# pam-controller.net
KiCad netlist of a schematic drawn in EAGLE
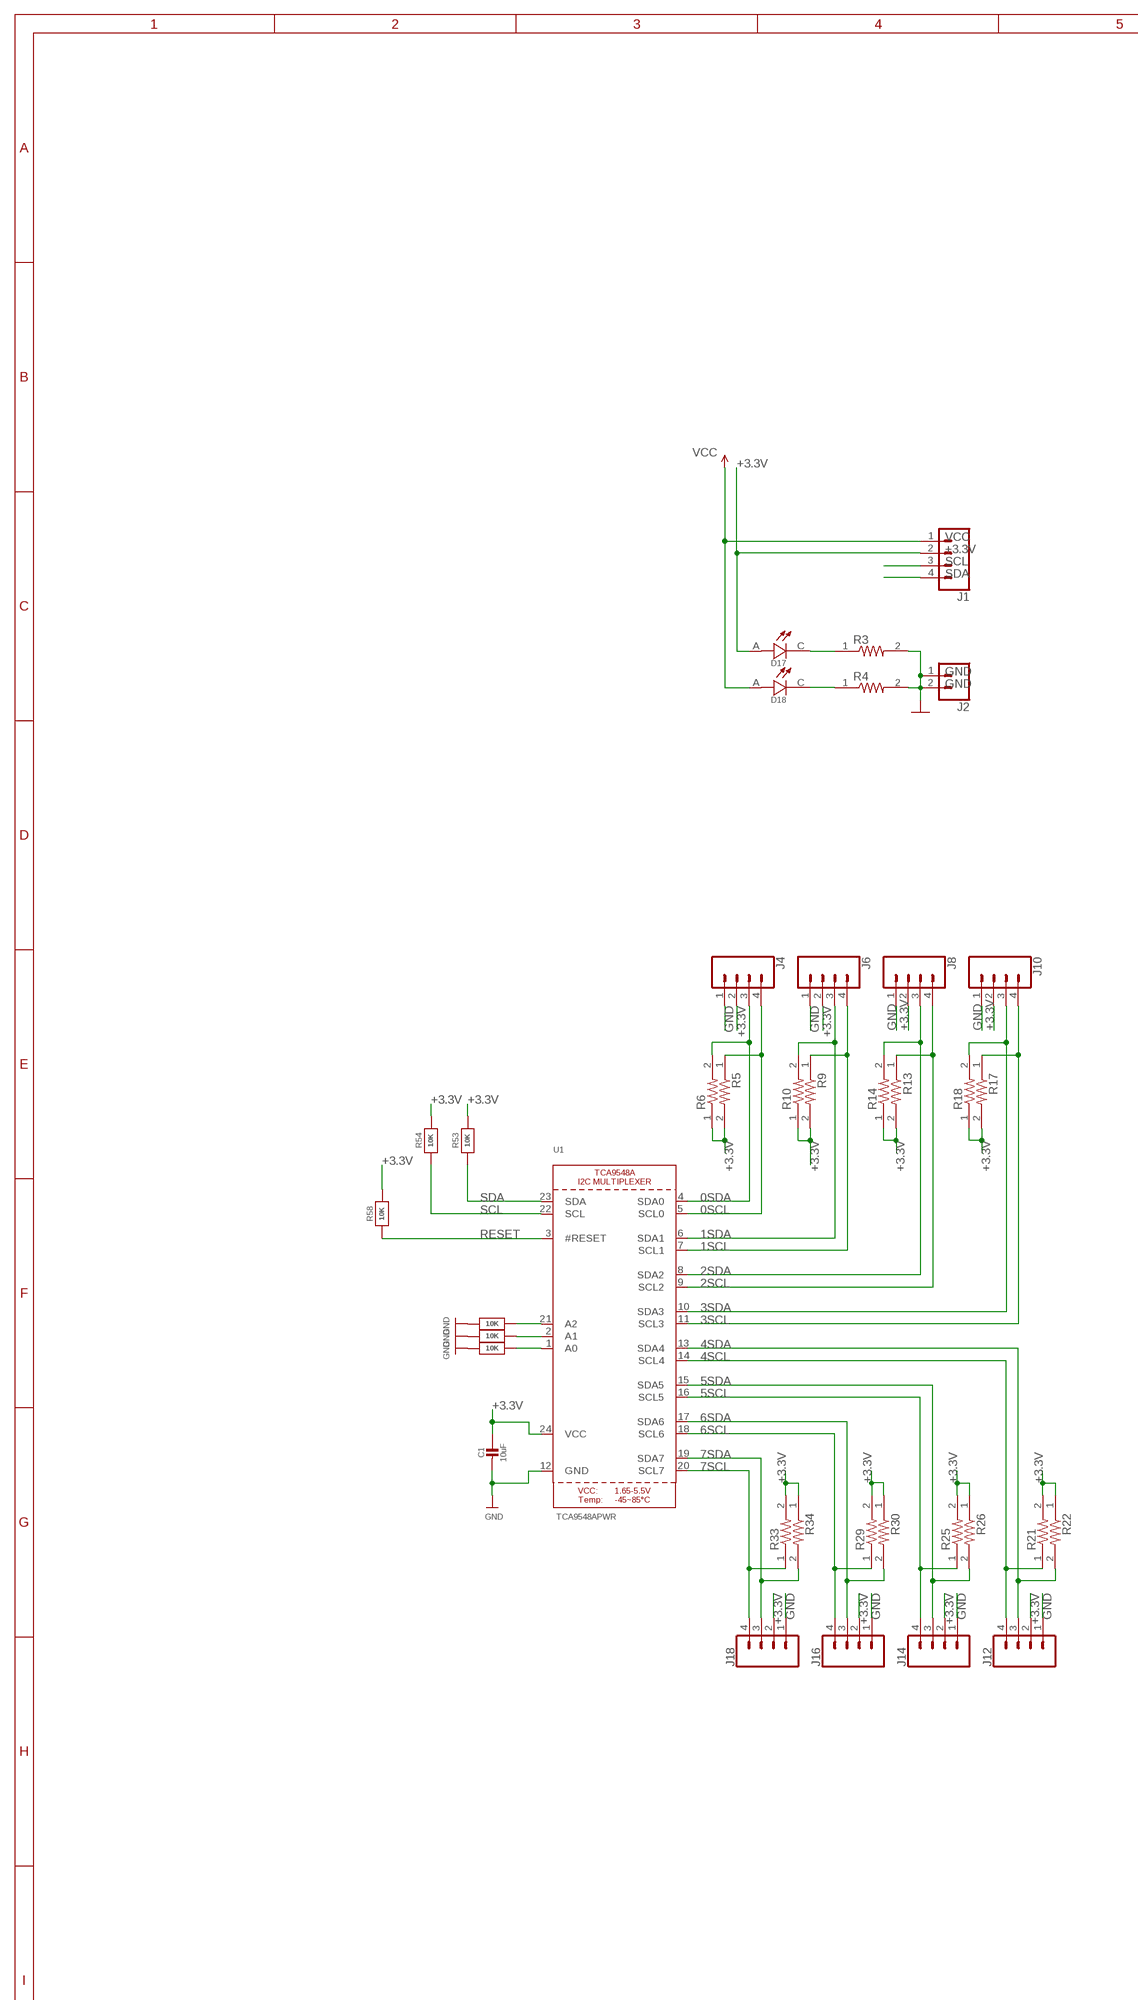
[diagram p0: schematic, sheet 1, part 1 of 2]
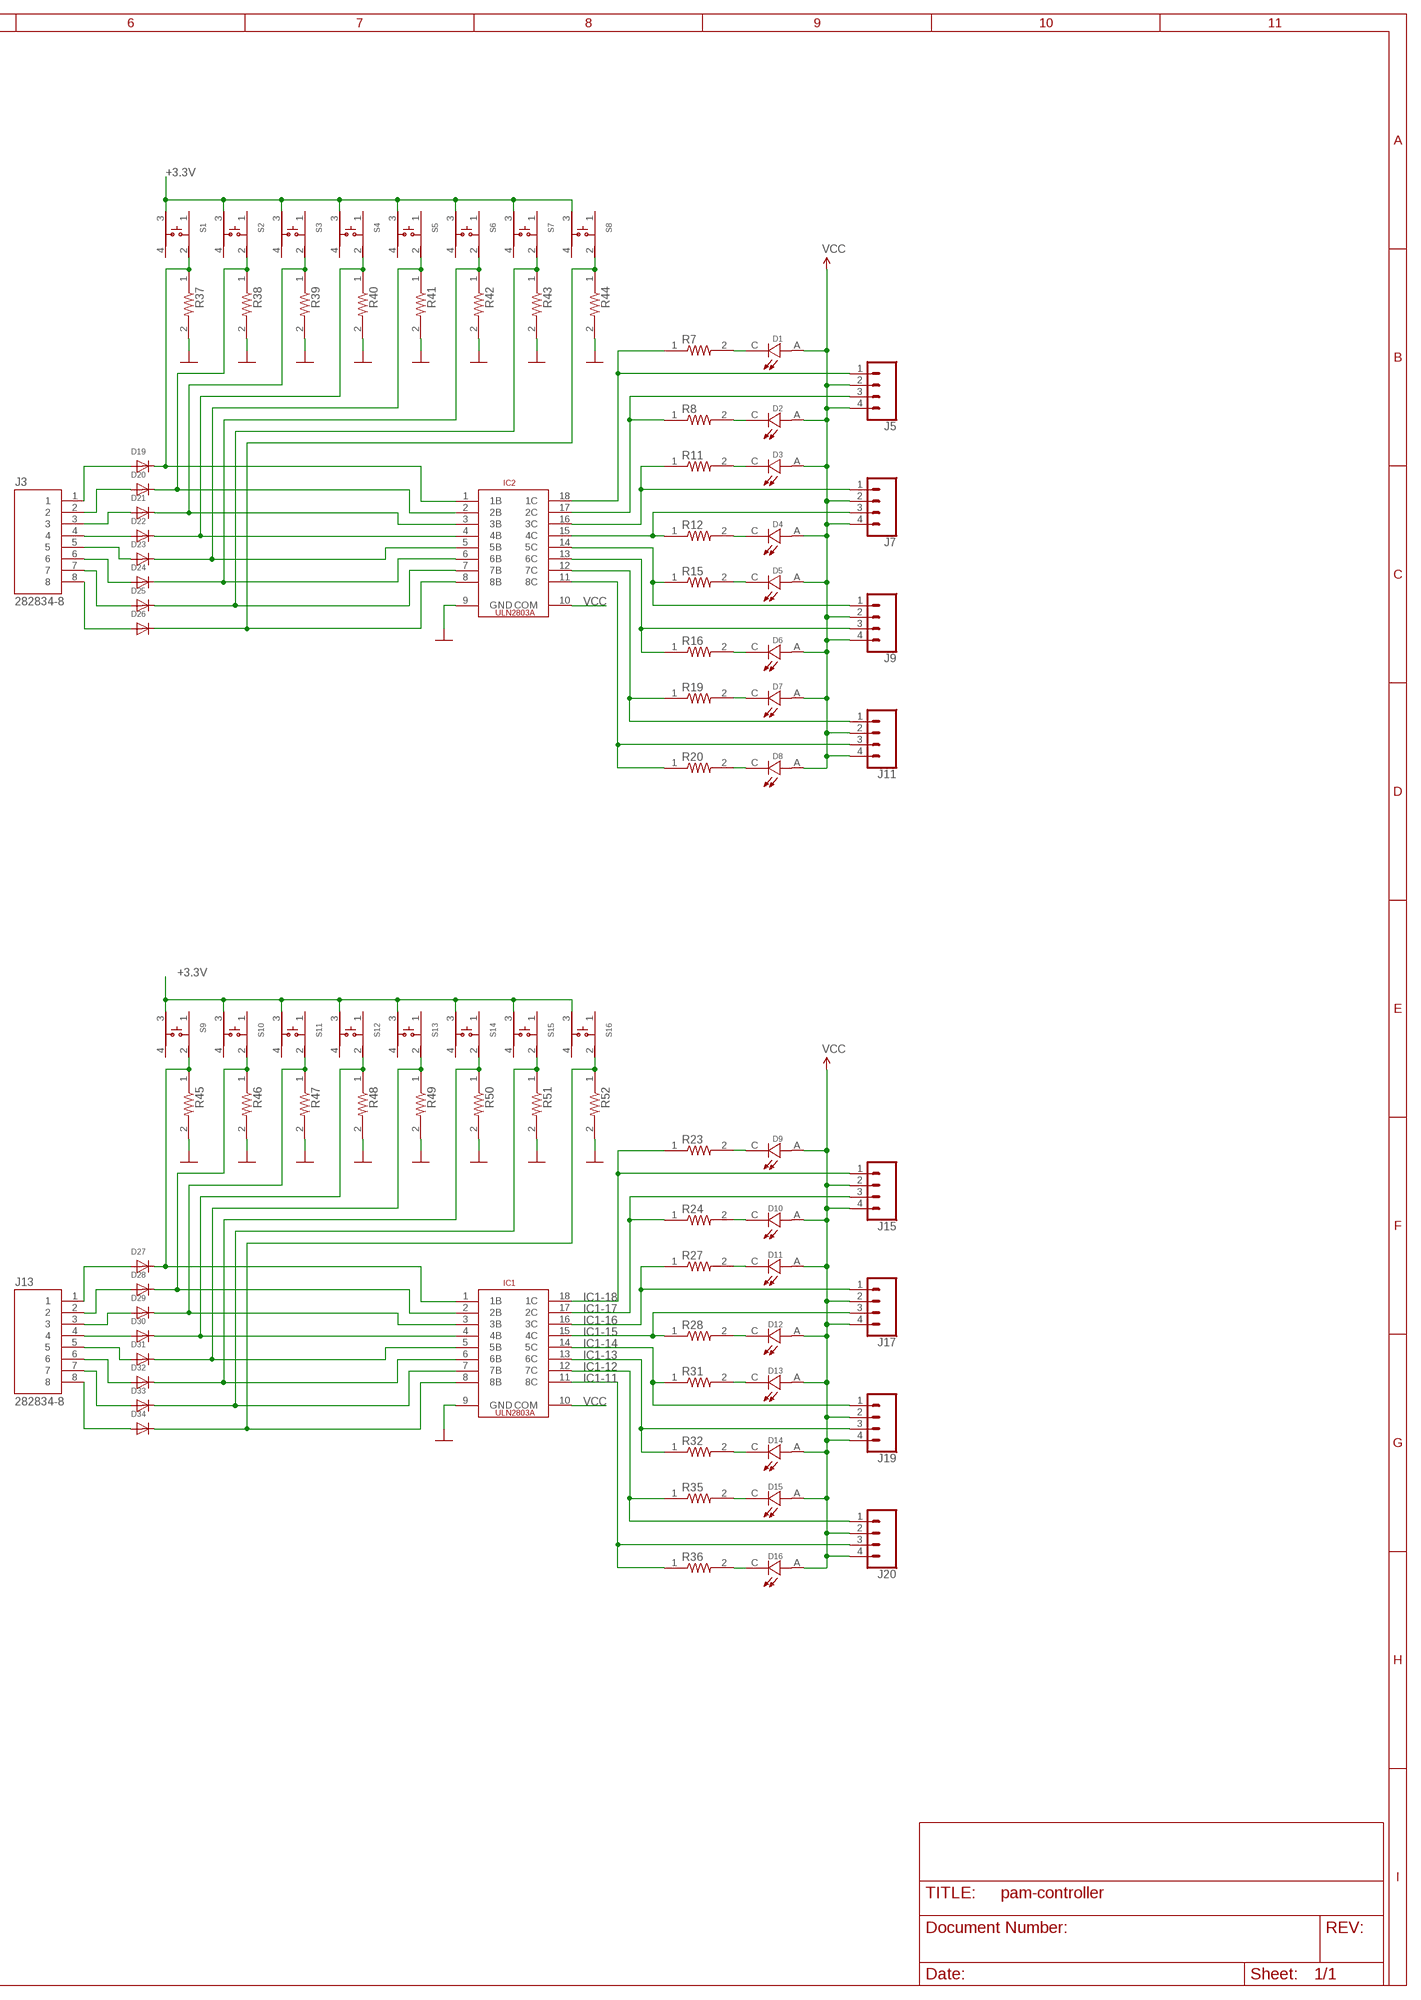
[diagram p1: schematic, sheet 1, part 2 of 2]

(export (version "E")
  (design (tool "Eeschema 10.0.6"))
  (components
    (comp (ref "C1")
      (value "10uF")
      (footprint "eagle-import:0805-NO")
      (libsource (lib "eagle-import") (part "CAP_CERAMIC0805-NOOUTLINE"))
    )
    (comp (ref "D1")
      (value "LTST-C190KGKT")
      (footprint "eagle-import:LEDC1608X35N")
      (libsource (lib "eagle-import") (part "LTST-C190KGKT"))
    )
    (comp (ref "D2")
      (value "LTST-C190KGKT")
      (footprint "eagle-import:LEDC1608X35N")
      (libsource (lib "eagle-import") (part "LTST-C190KGKT"))
    )
    (comp (ref "D3")
      (value "LTST-C190KGKT")
      (footprint "eagle-import:LEDC1608X35N")
      (libsource (lib "eagle-import") (part "LTST-C190KGKT"))
    )
    (comp (ref "D4")
      (value "LTST-C190KGKT")
      (footprint "eagle-import:LEDC1608X35N")
      (libsource (lib "eagle-import") (part "LTST-C190KGKT"))
    )
    (comp (ref "D5")
      (value "LTST-C190KGKT")
      (footprint "eagle-import:LEDC1608X35N")
      (libsource (lib "eagle-import") (part "LTST-C190KGKT"))
    )
    (comp (ref "D6")
      (value "LTST-C190KGKT")
      (footprint "eagle-import:LEDC1608X35N")
      (libsource (lib "eagle-import") (part "LTST-C190KGKT"))
    )
    (comp (ref "D7")
      (value "LTST-C190KGKT")
      (footprint "eagle-import:LEDC1608X35N")
      (libsource (lib "eagle-import") (part "LTST-C190KGKT"))
    )
    (comp (ref "D8")
      (value "LTST-C190KGKT")
      (footprint "eagle-import:LEDC1608X35N")
      (libsource (lib "eagle-import") (part "LTST-C190KGKT"))
    )
    (comp (ref "D9")
      (value "LTST-C190KGKT")
      (footprint "eagle-import:LEDC1608X35N")
      (libsource (lib "eagle-import") (part "LTST-C190KGKT"))
    )
    (comp (ref "D10")
      (value "LTST-C190KGKT")
      (footprint "eagle-import:LEDC1608X35N")
      (libsource (lib "eagle-import") (part "LTST-C190KGKT"))
    )
    (comp (ref "D11")
      (value "LTST-C190KGKT")
      (footprint "eagle-import:LEDC1608X35N")
      (libsource (lib "eagle-import") (part "LTST-C190KGKT"))
    )
    (comp (ref "D12")
      (value "LTST-C190KGKT")
      (footprint "eagle-import:LEDC1608X35N")
      (libsource (lib "eagle-import") (part "LTST-C190KGKT"))
    )
    (comp (ref "D13")
      (value "LTST-C190KGKT")
      (footprint "eagle-import:LEDC1608X35N")
      (libsource (lib "eagle-import") (part "LTST-C190KGKT"))
    )
    (comp (ref "D14")
      (value "LTST-C190KGKT")
      (footprint "eagle-import:LEDC1608X35N")
      (libsource (lib "eagle-import") (part "LTST-C190KGKT"))
    )
    (comp (ref "D15")
      (value "LTST-C190KGKT")
      (footprint "eagle-import:LEDC1608X35N")
      (libsource (lib "eagle-import") (part "LTST-C190KGKT"))
    )
    (comp (ref "D16")
      (value "LTST-C190KGKT")
      (footprint "eagle-import:LEDC1608X35N")
      (libsource (lib "eagle-import") (part "LTST-C190KGKT"))
    )
    (comp (ref "D17")
      (value "LTST-C190KGKT")
      (footprint "eagle-import:LEDC1608X35N")
      (libsource (lib "eagle-import") (part "LTST-C190KGKT"))
    )
    (comp (ref "D18")
      (value "LTST-C190KGKT")
      (footprint "eagle-import:LEDC1608X35N")
      (libsource (lib "eagle-import") (part "LTST-C190KGKT"))
    )
    (comp (ref "D19")
      (value "DIODESOD-523")
      (footprint "eagle-import:SOD-523")
      (libsource (lib "eagle-import") (part "DIODESOD-523"))
    )
    (comp (ref "D20")
      (value "DIODESOD-523")
      (footprint "eagle-import:SOD-523")
      (libsource (lib "eagle-import") (part "DIODESOD-523"))
    )
    (comp (ref "D21")
      (value "DIODESOD-523")
      (footprint "eagle-import:SOD-523")
      (libsource (lib "eagle-import") (part "DIODESOD-523"))
    )
    (comp (ref "D22")
      (value "DIODESOD-523")
      (footprint "eagle-import:SOD-523")
      (libsource (lib "eagle-import") (part "DIODESOD-523"))
    )
    (comp (ref "D23")
      (value "DIODESOD-523")
      (footprint "eagle-import:SOD-523")
      (libsource (lib "eagle-import") (part "DIODESOD-523"))
    )
    (comp (ref "D24")
      (value "DIODESOD-523")
      (footprint "eagle-import:SOD-523")
      (libsource (lib "eagle-import") (part "DIODESOD-523"))
    )
    (comp (ref "D25")
      (value "DIODESOD-523")
      (footprint "eagle-import:SOD-523")
      (libsource (lib "eagle-import") (part "DIODESOD-523"))
    )
    (comp (ref "D26")
      (value "DIODESOD-523")
      (footprint "eagle-import:SOD-523")
      (libsource (lib "eagle-import") (part "DIODESOD-523"))
    )
    (comp (ref "D27")
      (value "DIODESOD-523")
      (footprint "eagle-import:SOD-523")
      (libsource (lib "eagle-import") (part "DIODESOD-523"))
    )
    (comp (ref "D28")
      (value "DIODESOD-523")
      (footprint "eagle-import:SOD-523")
      (libsource (lib "eagle-import") (part "DIODESOD-523"))
    )
    (comp (ref "D29")
      (value "DIODESOD-523")
      (footprint "eagle-import:SOD-523")
      (libsource (lib "eagle-import") (part "DIODESOD-523"))
    )
    (comp (ref "D30")
      (value "DIODESOD-523")
      (footprint "eagle-import:SOD-523")
      (libsource (lib "eagle-import") (part "DIODESOD-523"))
    )
    (comp (ref "D31")
      (value "DIODESOD-523")
      (footprint "eagle-import:SOD-523")
      (libsource (lib "eagle-import") (part "DIODESOD-523"))
    )
    (comp (ref "D32")
      (value "DIODESOD-523")
      (footprint "eagle-import:SOD-523")
      (libsource (lib "eagle-import") (part "DIODESOD-523"))
    )
    (comp (ref "D33")
      (value "DIODESOD-523")
      (footprint "eagle-import:SOD-523")
      (libsource (lib "eagle-import") (part "DIODESOD-523"))
    )
    (comp (ref "D34")
      (value "DIODESOD-523")
      (footprint "eagle-import:SOD-523")
      (libsource (lib "eagle-import") (part "DIODESOD-523"))
    )
    (comp (ref "IC1")
      (value "ULN2803A")
      (footprint "eagle-import:ULN2803A")
      (fields (field (name "MF") "STMicroelectronics"))
      (libsource (lib "eagle-import") (part "ULN2803A"))
    )
    (comp (ref "IC2")
      (value "ULN2803A")
      (footprint "eagle-import:ULN2803A")
      (fields (field (name "MF") "STMicroelectronics"))
      (libsource (lib "eagle-import") (part "ULN2803A"))
    )
    (comp (ref "J1")
      (value "CONN_04POLAR")
      (footprint "eagle-import:MOLEX-1X4")
      (libsource (lib "eagle-import") (part "CONN_04POLAR"))
    )
    (comp (ref "J2")
      (value "CONN_02POLAR")
      (footprint "eagle-import:MOLEX-1X2")
      (libsource (lib "eagle-import") (part "CONN_02POLAR"))
    )
    (comp (ref "J3")
      (value "282834-8")
      (footprint "eagle-import:TE_282834-8")
      (fields (field (name "MANUFACTURER") "TE Connectivity"))
      (libsource (lib "eagle-import") (part "282834-8"))
    )
    (comp (ref "J4")
      (value "CONN_04POLAR")
      (footprint "eagle-import:MOLEX-1X4")
      (libsource (lib "eagle-import") (part "CONN_04POLAR"))
    )
    (comp (ref "J5")
      (value "CONN_04POLAR")
      (footprint "eagle-import:MOLEX-1X4")
      (libsource (lib "eagle-import") (part "CONN_04POLAR"))
    )
    (comp (ref "J6")
      (value "CONN_04POLAR")
      (footprint "eagle-import:MOLEX-1X4")
      (libsource (lib "eagle-import") (part "CONN_04POLAR"))
    )
    (comp (ref "J7")
      (value "CONN_04POLAR")
      (footprint "eagle-import:MOLEX-1X4")
      (libsource (lib "eagle-import") (part "CONN_04POLAR"))
    )
    (comp (ref "J8")
      (value "CONN_04POLAR")
      (footprint "eagle-import:MOLEX-1X4")
      (libsource (lib "eagle-import") (part "CONN_04POLAR"))
    )
    (comp (ref "J9")
      (value "CONN_04POLAR")
      (footprint "eagle-import:MOLEX-1X4")
      (libsource (lib "eagle-import") (part "CONN_04POLAR"))
    )
    (comp (ref "J10")
      (value "CONN_04POLAR")
      (footprint "eagle-import:MOLEX-1X4")
      (libsource (lib "eagle-import") (part "CONN_04POLAR"))
    )
    (comp (ref "J11")
      (value "CONN_04POLAR")
      (footprint "eagle-import:MOLEX-1X4")
      (libsource (lib "eagle-import") (part "CONN_04POLAR"))
    )
    (comp (ref "J12")
      (value "CONN_04POLAR")
      (footprint "eagle-import:MOLEX-1X4")
      (libsource (lib "eagle-import") (part "CONN_04POLAR"))
    )
    (comp (ref "J13")
      (value "282834-8")
      (footprint "eagle-import:TE_282834-8")
      (fields (field (name "MANUFACTURER") "TE Connectivity"))
      (libsource (lib "eagle-import") (part "282834-8"))
    )
    (comp (ref "J14")
      (value "CONN_04POLAR")
      (footprint "eagle-import:MOLEX-1X4")
      (libsource (lib "eagle-import") (part "CONN_04POLAR"))
    )
    (comp (ref "J15")
      (value "CONN_04POLAR")
      (footprint "eagle-import:MOLEX-1X4")
      (libsource (lib "eagle-import") (part "CONN_04POLAR"))
    )
    (comp (ref "J16")
      (value "CONN_04POLAR")
      (footprint "eagle-import:MOLEX-1X4")
      (libsource (lib "eagle-import") (part "CONN_04POLAR"))
    )
    (comp (ref "J17")
      (value "CONN_04POLAR")
      (footprint "eagle-import:MOLEX-1X4")
      (libsource (lib "eagle-import") (part "CONN_04POLAR"))
    )
    (comp (ref "J18")
      (value "CONN_04POLAR")
      (footprint "eagle-import:MOLEX-1X4")
      (libsource (lib "eagle-import") (part "CONN_04POLAR"))
    )
    (comp (ref "J19")
      (value "CONN_04POLAR")
      (footprint "eagle-import:MOLEX-1X4")
      (libsource (lib "eagle-import") (part "CONN_04POLAR"))
    )
    (comp (ref "J20")
      (value "CONN_04POLAR")
      (footprint "eagle-import:MOLEX-1X4")
      (libsource (lib "eagle-import") (part "CONN_04POLAR"))
    )
    (comp (ref "R3")
      (value "1K")
      (footprint "eagle-import:RESC1607X60N")
      (libsource (lib "eagle-import") (part "RC0603FR-071KL"))
    )
    (comp (ref "R4")
      (value "1K")
      (footprint "eagle-import:RESC1607X60N")
      (libsource (lib "eagle-import") (part "RC0603FR-071KL"))
    )
    (comp (ref "R5")
      (value "1K")
      (footprint "eagle-import:RESC1607X60N")
      (libsource (lib "eagle-import") (part "RC0603FR-071KL"))
    )
    (comp (ref "R6")
      (value "1K")
      (footprint "eagle-import:RESC1607X60N")
      (libsource (lib "eagle-import") (part "RC0603FR-071KL"))
    )
    (comp (ref "R7")
      (value "1K")
      (footprint "eagle-import:RESC1607X60N")
      (libsource (lib "eagle-import") (part "RC0603FR-071KL"))
    )
    (comp (ref "R8")
      (value "1K")
      (footprint "eagle-import:RESC1607X60N")
      (libsource (lib "eagle-import") (part "RC0603FR-071KL"))
    )
    (comp (ref "R9")
      (value "1K")
      (footprint "eagle-import:RESC1607X60N")
      (libsource (lib "eagle-import") (part "RC0603FR-071KL"))
    )
    (comp (ref "R10")
      (value "1K")
      (footprint "eagle-import:RESC1607X60N")
      (libsource (lib "eagle-import") (part "RC0603FR-071KL"))
    )
    (comp (ref "R11")
      (value "1K")
      (footprint "eagle-import:RESC1607X60N")
      (libsource (lib "eagle-import") (part "RC0603FR-071KL"))
    )
    (comp (ref "R12")
      (value "1K")
      (footprint "eagle-import:RESC1607X60N")
      (libsource (lib "eagle-import") (part "RC0603FR-071KL"))
    )
    (comp (ref "R13")
      (value "1K")
      (footprint "eagle-import:RESC1607X60N")
      (libsource (lib "eagle-import") (part "RC0603FR-071KL"))
    )
    (comp (ref "R14")
      (value "1K")
      (footprint "eagle-import:RESC1607X60N")
      (libsource (lib "eagle-import") (part "RC0603FR-071KL"))
    )
    (comp (ref "R15")
      (value "1K")
      (footprint "eagle-import:RESC1607X60N")
      (libsource (lib "eagle-import") (part "RC0603FR-071KL"))
    )
    (comp (ref "R16")
      (value "1K")
      (footprint "eagle-import:RESC1607X60N")
      (libsource (lib "eagle-import") (part "RC0603FR-071KL"))
    )
    (comp (ref "R17")
      (value "1K")
      (footprint "eagle-import:RESC1607X60N")
      (libsource (lib "eagle-import") (part "RC0603FR-071KL"))
    )
    (comp (ref "R18")
      (value "1K")
      (footprint "eagle-import:RESC1607X60N")
      (libsource (lib "eagle-import") (part "RC0603FR-071KL"))
    )
    (comp (ref "R19")
      (value "1K")
      (footprint "eagle-import:RESC1607X60N")
      (libsource (lib "eagle-import") (part "RC0603FR-071KL"))
    )
    (comp (ref "R20")
      (value "1K")
      (footprint "eagle-import:RESC1607X60N")
      (libsource (lib "eagle-import") (part "RC0603FR-071KL"))
    )
    (comp (ref "R21")
      (value "1K")
      (footprint "eagle-import:RESC1607X60N")
      (libsource (lib "eagle-import") (part "RC0603FR-071KL"))
    )
    (comp (ref "R22")
      (value "1K")
      (footprint "eagle-import:RESC1607X60N")
      (libsource (lib "eagle-import") (part "RC0603FR-071KL"))
    )
    (comp (ref "R23")
      (value "1K")
      (footprint "eagle-import:RESC1607X60N")
      (libsource (lib "eagle-import") (part "RC0603FR-071KL"))
    )
    (comp (ref "R24")
      (value "1K")
      (footprint "eagle-import:RESC1607X60N")
      (libsource (lib "eagle-import") (part "RC0603FR-071KL"))
    )
    (comp (ref "R25")
      (value "1K")
      (footprint "eagle-import:RESC1607X60N")
      (libsource (lib "eagle-import") (part "RC0603FR-071KL"))
    )
    (comp (ref "R26")
      (value "1K")
      (footprint "eagle-import:RESC1607X60N")
      (libsource (lib "eagle-import") (part "RC0603FR-071KL"))
    )
    (comp (ref "R27")
      (value "1K")
      (footprint "eagle-import:RESC1607X60N")
      (libsource (lib "eagle-import") (part "RC0603FR-071KL"))
    )
    (comp (ref "R28")
      (value "1K")
      (footprint "eagle-import:RESC1607X60N")
      (libsource (lib "eagle-import") (part "RC0603FR-071KL"))
    )
    (comp (ref "R29")
      (value "1K")
      (footprint "eagle-import:RESC1607X60N")
      (libsource (lib "eagle-import") (part "RC0603FR-071KL"))
    )
    (comp (ref "R30")
      (value "1K")
      (footprint "eagle-import:RESC1607X60N")
      (libsource (lib "eagle-import") (part "RC0603FR-071KL"))
    )
    (comp (ref "R31")
      (value "1K")
      (footprint "eagle-import:RESC1607X60N")
      (libsource (lib "eagle-import") (part "RC0603FR-071KL"))
    )
    (comp (ref "R32")
      (value "1K")
      (footprint "eagle-import:RESC1607X60N")
      (libsource (lib "eagle-import") (part "RC0603FR-071KL"))
    )
    (comp (ref "R33")
      (value "1K")
      (footprint "eagle-import:RESC1607X60N")
      (libsource (lib "eagle-import") (part "RC0603FR-071KL"))
    )
    (comp (ref "R34")
      (value "1K")
      (footprint "eagle-import:RESC1607X60N")
      (libsource (lib "eagle-import") (part "RC0603FR-071KL"))
    )
    (comp (ref "R35")
      (value "1K")
      (footprint "eagle-import:RESC1607X60N")
      (libsource (lib "eagle-import") (part "RC0603FR-071KL"))
    )
    (comp (ref "R36")
      (value "1K")
      (footprint "eagle-import:RESC1607X60N")
      (libsource (lib "eagle-import") (part "RC0603FR-071KL"))
    )
    (comp (ref "R37")
      (value "1K")
      (footprint "eagle-import:RESC1607X60N")
      (libsource (lib "eagle-import") (part "RC0603FR-071KL"))
    )
    (comp (ref "R38")
      (value "1K")
      (footprint "eagle-import:RESC1607X60N")
      (libsource (lib "eagle-import") (part "RC0603FR-071KL"))
    )
    (comp (ref "R39")
      (value "1K")
      (footprint "eagle-import:RESC1607X60N")
      (libsource (lib "eagle-import") (part "RC0603FR-071KL"))
    )
    (comp (ref "R40")
      (value "1K")
      (footprint "eagle-import:RESC1607X60N")
      (libsource (lib "eagle-import") (part "RC0603FR-071KL"))
    )
    (comp (ref "R41")
      (value "1K")
      (footprint "eagle-import:RESC1607X60N")
      (libsource (lib "eagle-import") (part "RC0603FR-071KL"))
    )
    (comp (ref "R42")
      (value "1K")
      (footprint "eagle-import:RESC1607X60N")
      (libsource (lib "eagle-import") (part "RC0603FR-071KL"))
    )
    (comp (ref "R43")
      (value "1K")
      (footprint "eagle-import:RESC1607X60N")
      (libsource (lib "eagle-import") (part "RC0603FR-071KL"))
    )
    (comp (ref "R44")
      (value "1K")
      (footprint "eagle-import:RESC1607X60N")
      (libsource (lib "eagle-import") (part "RC0603FR-071KL"))
    )
    (comp (ref "R45")
      (value "1K")
      (footprint "eagle-import:RESC1607X60N")
      (libsource (lib "eagle-import") (part "RC0603FR-071KL"))
    )
    (comp (ref "R46")
      (value "1K")
      (footprint "eagle-import:RESC1607X60N")
      (libsource (lib "eagle-import") (part "RC0603FR-071KL"))
    )
    (comp (ref "R47")
      (value "1K")
      (footprint "eagle-import:RESC1607X60N")
      (libsource (lib "eagle-import") (part "RC0603FR-071KL"))
    )
    (comp (ref "R48")
      (value "1K")
      (footprint "eagle-import:RESC1607X60N")
      (libsource (lib "eagle-import") (part "RC0603FR-071KL"))
    )
    (comp (ref "R49")
      (value "1K")
      (footprint "eagle-import:RESC1607X60N")
      (libsource (lib "eagle-import") (part "RC0603FR-071KL"))
    )
    (comp (ref "R50")
      (value "1K")
      (footprint "eagle-import:RESC1607X60N")
      (libsource (lib "eagle-import") (part "RC0603FR-071KL"))
    )
    (comp (ref "R51")
      (value "1K")
      (footprint "eagle-import:RESC1607X60N")
      (libsource (lib "eagle-import") (part "RC0603FR-071KL"))
    )
    (comp (ref "R52")
      (value "1K")
      (footprint "eagle-import:RESC1607X60N")
      (libsource (lib "eagle-import") (part "RC0603FR-071KL"))
    )
    (comp (ref "R53")
      (value "10K")
      (footprint "eagle-import:0805-NO")
      (libsource (lib "eagle-import") (part "RESISTOR0805_NOOUTLINE"))
    )
    (comp (ref "R54")
      (value "10K")
      (footprint "eagle-import:0805-NO")
      (libsource (lib "eagle-import") (part "RESISTOR0805_NOOUTLINE"))
    )
    (comp (ref "R55")
      (value "10K")
      (footprint "eagle-import:0805-NO")
      (libsource (lib "eagle-import") (part "RESISTOR0805_NOOUTLINE"))
    )
    (comp (ref "R56")
      (value "10K")
      (footprint "eagle-import:0805-NO")
      (libsource (lib "eagle-import") (part "RESISTOR0805_NOOUTLINE"))
    )
    (comp (ref "R57")
      (value "10K")
      (footprint "eagle-import:0805-NO")
      (libsource (lib "eagle-import") (part "RESISTOR0805_NOOUTLINE"))
    )
    (comp (ref "R58")
      (value "10K")
      (footprint "eagle-import:0805-NO")
      (libsource (lib "eagle-import") (part "RESISTOR0805_NOOUTLINE"))
    )
    (comp (ref "S1")
      (value "SKRPACE010")
      (footprint "eagle-import:SW_SKRPACE010")
      (fields (field (name "MANUFACTURER") "ALPS"))
      (libsource (lib "eagle-import") (part "SKRPACE010"))
    )
    (comp (ref "S2")
      (value "SKRPACE010")
      (footprint "eagle-import:SW_SKRPACE010")
      (fields (field (name "MANUFACTURER") "ALPS"))
      (libsource (lib "eagle-import") (part "SKRPACE010"))
    )
    (comp (ref "S3")
      (value "SKRPACE010")
      (footprint "eagle-import:SW_SKRPACE010")
      (fields (field (name "MANUFACTURER") "ALPS"))
      (libsource (lib "eagle-import") (part "SKRPACE010"))
    )
    (comp (ref "S4")
      (value "SKRPACE010")
      (footprint "eagle-import:SW_SKRPACE010")
      (fields (field (name "MANUFACTURER") "ALPS"))
      (libsource (lib "eagle-import") (part "SKRPACE010"))
    )
    (comp (ref "S5")
      (value "SKRPACE010")
      (footprint "eagle-import:SW_SKRPACE010")
      (fields (field (name "MANUFACTURER") "ALPS"))
      (libsource (lib "eagle-import") (part "SKRPACE010"))
    )
    (comp (ref "S6")
      (value "SKRPACE010")
      (footprint "eagle-import:SW_SKRPACE010")
      (fields (field (name "MANUFACTURER") "ALPS"))
      (libsource (lib "eagle-import") (part "SKRPACE010"))
    )
    (comp (ref "S7")
      (value "SKRPACE010")
      (footprint "eagle-import:SW_SKRPACE010")
      (fields (field (name "MANUFACTURER") "ALPS"))
      (libsource (lib "eagle-import") (part "SKRPACE010"))
    )
    (comp (ref "S8")
      (value "SKRPACE010")
      (footprint "eagle-import:SW_SKRPACE010")
      (fields (field (name "MANUFACTURER") "ALPS"))
      (libsource (lib "eagle-import") (part "SKRPACE010"))
    )
    (comp (ref "S9")
      (value "SKRPACE010")
      (footprint "eagle-import:SW_SKRPACE010")
      (fields (field (name "MANUFACTURER") "ALPS"))
      (libsource (lib "eagle-import") (part "SKRPACE010"))
    )
    (comp (ref "S10")
      (value "SKRPACE010")
      (footprint "eagle-import:SW_SKRPACE010")
      (fields (field (name "MANUFACTURER") "ALPS"))
      (libsource (lib "eagle-import") (part "SKRPACE010"))
    )
    (comp (ref "S11")
      (value "SKRPACE010")
      (footprint "eagle-import:SW_SKRPACE010")
      (fields (field (name "MANUFACTURER") "ALPS"))
      (libsource (lib "eagle-import") (part "SKRPACE010"))
    )
    (comp (ref "S12")
      (value "SKRPACE010")
      (footprint "eagle-import:SW_SKRPACE010")
      (fields (field (name "MANUFACTURER") "ALPS"))
      (libsource (lib "eagle-import") (part "SKRPACE010"))
    )
    (comp (ref "S13")
      (value "SKRPACE010")
      (footprint "eagle-import:SW_SKRPACE010")
      (fields (field (name "MANUFACTURER") "ALPS"))
      (libsource (lib "eagle-import") (part "SKRPACE010"))
    )
    (comp (ref "S14")
      (value "SKRPACE010")
      (footprint "eagle-import:SW_SKRPACE010")
      (fields (field (name "MANUFACTURER") "ALPS"))
      (libsource (lib "eagle-import") (part "SKRPACE010"))
    )
    (comp (ref "S15")
      (value "SKRPACE010")
      (footprint "eagle-import:SW_SKRPACE010")
      (fields (field (name "MANUFACTURER") "ALPS"))
      (libsource (lib "eagle-import") (part "SKRPACE010"))
    )
    (comp (ref "S16")
      (value "SKRPACE010")
      (footprint "eagle-import:SW_SKRPACE010")
      (fields (field (name "MANUFACTURER") "ALPS"))
      (libsource (lib "eagle-import") (part "SKRPACE010"))
    )
    (comp (ref "U1")
      (value "TCA9548APWR")
      (footprint "eagle-import:TSSOP24")
      (libsource (lib "eagle-import") (part "TCA9548A"))
    )
  )
  (nets
    (net (code "1") (name "/+3.3V") (class "Default")
      (node (ref "C1") (pin "1") (pinfunction "1_1") (pintype "passive"))
      (node (ref "D17") (pin "A") (pinfunction "A_A") (pintype "passive"))
      (node (ref "J1") (pin "2") (pinfunction "2_2") (pintype "passive"))
      (node (ref "J10") (pin "2") (pinfunction "2_2") (pintype "passive"))
      (node (ref "J12") (pin "2") (pinfunction "2_2") (pintype "passive"))
      (node (ref "J14") (pin "2") (pinfunction "2_2") (pintype "passive"))
      (node (ref "J16") (pin "2") (pinfunction "2_2") (pintype "passive"))
      (node (ref "J18") (pin "2") (pinfunction "2_2") (pintype "passive"))
      (node (ref "J4") (pin "2") (pinfunction "2_2") (pintype "passive"))
      (node (ref "J6") (pin "2") (pinfunction "2_2") (pintype "passive"))
      (node (ref "J8") (pin "2") (pinfunction "2_2") (pintype "passive"))
      (node (ref "R10") (pin "1") (pinfunction "1_1") (pintype "passive"))
      (node (ref "R13") (pin "2") (pinfunction "2_2") (pintype "passive"))
      (node (ref "R14") (pin "1") (pinfunction "1_1") (pintype "passive"))
      (node (ref "R17") (pin "2") (pinfunction "2_2") (pintype "passive"))
      (node (ref "R18") (pin "1") (pinfunction "1_1") (pintype "passive"))
      (node (ref "R21") (pin "2") (pinfunction "2_2") (pintype "passive"))
      (node (ref "R22") (pin "1") (pinfunction "1_1") (pintype "passive"))
      (node (ref "R25") (pin "2") (pinfunction "2_2") (pintype "passive"))
      (node (ref "R26") (pin "1") (pinfunction "1_1") (pintype "passive"))
      (node (ref "R29") (pin "2") (pinfunction "2_2") (pintype "passive"))
      (node (ref "R30") (pin "1") (pinfunction "1_1") (pintype "passive"))
      (node (ref "R33") (pin "2") (pinfunction "2_2") (pintype "passive"))
      (node (ref "R34") (pin "1") (pinfunction "1_1") (pintype "passive"))
      (node (ref "R5") (pin "2") (pinfunction "2_2") (pintype "passive"))
      (node (ref "R53") (pin "2") (pinfunction "2_2") (pintype "passive"))
      (node (ref "R54") (pin "2") (pinfunction "2_2") (pintype "passive"))
      (node (ref "R58") (pin "2") (pinfunction "2_2") (pintype "passive"))
      (node (ref "R6") (pin "1") (pinfunction "1_1") (pintype "passive"))
      (node (ref "R9") (pin "2") (pinfunction "2_2") (pintype "passive"))
      (node (ref "S1") (pin "3") (pinfunction "3_3") (pintype "bidirectional"))
      (node (ref "S10") (pin "3") (pinfunction "3_3") (pintype "bidirectional"))
      (node (ref "S11") (pin "3") (pinfunction "3_3") (pintype "bidirectional"))
      (node (ref "S12") (pin "3") (pinfunction "3_3") (pintype "bidirectional"))
      (node (ref "S13") (pin "3") (pinfunction "3_3") (pintype "bidirectional"))
      (node (ref "S14") (pin "3") (pinfunction "3_3") (pintype "bidirectional"))
      (node (ref "S15") (pin "3") (pinfunction "3_3") (pintype "bidirectional"))
      (node (ref "S16") (pin "3") (pinfunction "3_3") (pintype "bidirectional"))
      (node (ref "S2") (pin "3") (pinfunction "3_3") (pintype "bidirectional"))
      (node (ref "S3") (pin "3") (pinfunction "3_3") (pintype "bidirectional"))
      (node (ref "S4") (pin "3") (pinfunction "3_3") (pintype "bidirectional"))
      (node (ref "S5") (pin "3") (pinfunction "3_3") (pintype "bidirectional"))
      (node (ref "S6") (pin "3") (pinfunction "3_3") (pintype "bidirectional"))
      (node (ref "S7") (pin "3") (pinfunction "3_3") (pintype "bidirectional"))
      (node (ref "S8") (pin "3") (pinfunction "3_3") (pintype "bidirectional"))
      (node (ref "S9") (pin "3") (pinfunction "3_3") (pintype "bidirectional"))
      (node (ref "U1") (pin "24") (pinfunction "VCC_24") (pintype "bidirectional"))
    )
    (net (code "2") (name "/0SCL") (class "Default")
      (node (ref "J4") (pin "4") (pinfunction "4_4") (pintype "passive"))
      (node (ref "R5") (pin "1") (pinfunction "1_1") (pintype "passive"))
      (node (ref "U1") (pin "5") (pinfunction "SCL0_5") (pintype "bidirectional"))
    )
    (net (code "3") (name "/0SDA") (class "Default")
      (node (ref "J4") (pin "3") (pinfunction "3_3") (pintype "passive"))
      (node (ref "R6") (pin "2") (pinfunction "2_2") (pintype "passive"))
      (node (ref "U1") (pin "4") (pinfunction "SDA0_4") (pintype "bidirectional"))
    )
    (net (code "4") (name "/1SCL") (class "Default")
      (node (ref "J6") (pin "4") (pinfunction "4_4") (pintype "passive"))
      (node (ref "R9") (pin "1") (pinfunction "1_1") (pintype "passive"))
      (node (ref "U1") (pin "7") (pinfunction "SCL1_7") (pintype "bidirectional"))
    )
    (net (code "5") (name "/1SDA") (class "Default")
      (node (ref "J6") (pin "3") (pinfunction "3_3") (pintype "passive"))
      (node (ref "R10") (pin "2") (pinfunction "2_2") (pintype "passive"))
      (node (ref "U1") (pin "6") (pinfunction "SDA1_6") (pintype "bidirectional"))
    )
    (net (code "6") (name "/2SCL") (class "Default")
      (node (ref "J8") (pin "4") (pinfunction "4_4") (pintype "passive"))
      (node (ref "R13") (pin "1") (pinfunction "1_1") (pintype "passive"))
      (node (ref "U1") (pin "9") (pinfunction "SCL2_9") (pintype "bidirectional"))
    )
    (net (code "7") (name "/2SDA") (class "Default")
      (node (ref "J8") (pin "3") (pinfunction "3_3") (pintype "passive"))
      (node (ref "R14") (pin "2") (pinfunction "2_2") (pintype "passive"))
      (node (ref "U1") (pin "8") (pinfunction "SDA2_8") (pintype "bidirectional"))
    )
    (net (code "8") (name "/3SCL") (class "Default")
      (node (ref "J10") (pin "4") (pinfunction "4_4") (pintype "passive"))
      (node (ref "R17") (pin "1") (pinfunction "1_1") (pintype "passive"))
      (node (ref "U1") (pin "11") (pinfunction "SCL3_11") (pintype "bidirectional"))
    )
    (net (code "9") (name "/3SDA") (class "Default")
      (node (ref "J10") (pin "3") (pinfunction "3_3") (pintype "passive"))
      (node (ref "R18") (pin "2") (pinfunction "2_2") (pintype "passive"))
      (node (ref "U1") (pin "10") (pinfunction "SDA3_10") (pintype "bidirectional"))
    )
    (net (code "10") (name "/4SCL") (class "Default")
      (node (ref "J12") (pin "4") (pinfunction "4_4") (pintype "passive"))
      (node (ref "R21") (pin "1") (pinfunction "1_1") (pintype "passive"))
      (node (ref "U1") (pin "14") (pinfunction "SCL4_14") (pintype "bidirectional"))
    )
    (net (code "11") (name "/4SDA") (class "Default")
      (node (ref "J12") (pin "3") (pinfunction "3_3") (pintype "passive"))
      (node (ref "R22") (pin "2") (pinfunction "2_2") (pintype "passive"))
      (node (ref "U1") (pin "13") (pinfunction "SDA4_13") (pintype "bidirectional"))
    )
    (net (code "12") (name "/5SCL") (class "Default")
      (node (ref "J14") (pin "4") (pinfunction "4_4") (pintype "passive"))
      (node (ref "R25") (pin "1") (pinfunction "1_1") (pintype "passive"))
      (node (ref "U1") (pin "16") (pinfunction "SCL5_16") (pintype "bidirectional"))
    )
    (net (code "13") (name "/5SDA") (class "Default")
      (node (ref "J14") (pin "3") (pinfunction "3_3") (pintype "passive"))
      (node (ref "R26") (pin "2") (pinfunction "2_2") (pintype "passive"))
      (node (ref "U1") (pin "15") (pinfunction "SDA5_15") (pintype "bidirectional"))
    )
    (net (code "14") (name "/6SCL") (class "Default")
      (node (ref "J16") (pin "4") (pinfunction "4_4") (pintype "passive"))
      (node (ref "R29") (pin "1") (pinfunction "1_1") (pintype "passive"))
      (node (ref "U1") (pin "18") (pinfunction "SCL6_18") (pintype "bidirectional"))
    )
    (net (code "15") (name "/6SDA") (class "Default")
      (node (ref "J16") (pin "3") (pinfunction "3_3") (pintype "passive"))
      (node (ref "R30") (pin "2") (pinfunction "2_2") (pintype "passive"))
      (node (ref "U1") (pin "17") (pinfunction "SDA6_17") (pintype "bidirectional"))
    )
    (net (code "16") (name "/7SCL") (class "Default")
      (node (ref "J18") (pin "4") (pinfunction "4_4") (pintype "passive"))
      (node (ref "R33") (pin "1") (pinfunction "1_1") (pintype "passive"))
      (node (ref "U1") (pin "20") (pinfunction "SCL7_20") (pintype "bidirectional"))
    )
    (net (code "17") (name "/7SDA") (class "Default")
      (node (ref "J18") (pin "3") (pinfunction "3_3") (pintype "passive"))
      (node (ref "R34") (pin "2") (pinfunction "2_2") (pintype "passive"))
      (node (ref "U1") (pin "19") (pinfunction "SDA7_19") (pintype "bidirectional"))
    )
    (net (code "18") (name "/IC1-11") (class "Default")
      (node (ref "IC1") (pin "11") (pinfunction "8C_11") (pintype "bidirectional"))
      (node (ref "J20") (pin "3") (pinfunction "3_3") (pintype "passive"))
      (node (ref "R36") (pin "1") (pinfunction "1_1") (pintype "passive"))
    )
    (net (code "19") (name "/IC1-12") (class "Default")
      (node (ref "IC1") (pin "12") (pinfunction "7C_12") (pintype "bidirectional"))
      (node (ref "J20") (pin "1") (pinfunction "1_1") (pintype "passive"))
      (node (ref "R35") (pin "1") (pinfunction "1_1") (pintype "passive"))
    )
    (net (code "20") (name "/IC1-13") (class "Default")
      (node (ref "IC1") (pin "13") (pinfunction "6C_13") (pintype "bidirectional"))
      (node (ref "J19") (pin "3") (pinfunction "3_3") (pintype "passive"))
      (node (ref "R32") (pin "1") (pinfunction "1_1") (pintype "passive"))
    )
    (net (code "21") (name "/IC1-14") (class "Default")
      (node (ref "IC1") (pin "14") (pinfunction "5C_14") (pintype "bidirectional"))
      (node (ref "J19") (pin "1") (pinfunction "1_1") (pintype "passive"))
      (node (ref "R31") (pin "1") (pinfunction "1_1") (pintype "passive"))
    )
    (net (code "22") (name "/IC1-15") (class "Default")
      (node (ref "IC1") (pin "15") (pinfunction "4C_15") (pintype "bidirectional"))
      (node (ref "J17") (pin "3") (pinfunction "3_3") (pintype "passive"))
      (node (ref "R28") (pin "1") (pinfunction "1_1") (pintype "passive"))
    )
    (net (code "23") (name "/IC1-16") (class "Default")
      (node (ref "IC1") (pin "16") (pinfunction "3C_16") (pintype "bidirectional"))
      (node (ref "J17") (pin "1") (pinfunction "1_1") (pintype "passive"))
      (node (ref "R27") (pin "1") (pinfunction "1_1") (pintype "passive"))
    )
    (net (code "24") (name "/IC1-17") (class "Default")
      (node (ref "IC1") (pin "17") (pinfunction "2C_17") (pintype "bidirectional"))
      (node (ref "J15") (pin "3") (pinfunction "3_3") (pintype "passive"))
      (node (ref "R24") (pin "1") (pinfunction "1_1") (pintype "passive"))
    )
    (net (code "25") (name "/IC1-18") (class "Default")
      (node (ref "IC1") (pin "18") (pinfunction "1C_18") (pintype "bidirectional"))
      (node (ref "J15") (pin "1") (pinfunction "1_1") (pintype "passive"))
      (node (ref "R23") (pin "1") (pinfunction "1_1") (pintype "passive"))
    )
    (net (code "26") (name "/RESET") (class "Default")
      (node (ref "R58") (pin "1") (pinfunction "1_1") (pintype "passive"))
      (node (ref "U1") (pin "3") (pinfunction "#RESET_3") (pintype "bidirectional"))
    )
    (net (code "27") (name "/SCL") (class "Default")
      (node (ref "J1") (pin "4") (pinfunction "4_4") (pintype "passive"))
      (node (ref "R54") (pin "1") (pinfunction "1_1") (pintype "passive"))
      (node (ref "U1") (pin "22") (pinfunction "SCL_22") (pintype "bidirectional"))
    )
    (net (code "28") (name "/SDA") (class "Default")
      (node (ref "J1") (pin "3") (pinfunction "3_3") (pintype "passive"))
      (node (ref "R53") (pin "1") (pinfunction "1_1") (pintype "passive"))
      (node (ref "U1") (pin "23") (pinfunction "SDA_23") (pintype "bidirectional"))
    )
    (net (code "29") (name "GND") (class "Default")
      (node (ref "C1") (pin "2") (pinfunction "2_2") (pintype "passive"))
      (node (ref "IC1") (pin "9") (pinfunction "GND_9") (pintype "bidirectional"))
      (node (ref "IC2") (pin "9") (pinfunction "GND_9") (pintype "bidirectional"))
      (node (ref "J10") (pin "1") (pinfunction "1_1") (pintype "passive"))
      (node (ref "J12") (pin "1") (pinfunction "1_1") (pintype "passive"))
      (node (ref "J14") (pin "1") (pinfunction "1_1") (pintype "passive"))
      (node (ref "J16") (pin "1") (pinfunction "1_1") (pintype "passive"))
      (node (ref "J18") (pin "1") (pinfunction "1_1") (pintype "passive"))
      (node (ref "J2") (pin "1") (pinfunction "1_1") (pintype "passive"))
      (node (ref "J2") (pin "2") (pinfunction "2_2") (pintype "passive"))
      (node (ref "J4") (pin "1") (pinfunction "1_1") (pintype "passive"))
      (node (ref "J6") (pin "1") (pinfunction "1_1") (pintype "passive"))
      (node (ref "J8") (pin "1") (pinfunction "1_1") (pintype "passive"))
      (node (ref "R3") (pin "2") (pinfunction "2_2") (pintype "passive"))
      (node (ref "R37") (pin "2") (pinfunction "2_2") (pintype "passive"))
      (node (ref "R38") (pin "2") (pinfunction "2_2") (pintype "passive"))
      (node (ref "R39") (pin "2") (pinfunction "2_2") (pintype "passive"))
      (node (ref "R4") (pin "2") (pinfunction "2_2") (pintype "passive"))
      (node (ref "R40") (pin "2") (pinfunction "2_2") (pintype "passive"))
      (node (ref "R41") (pin "2") (pinfunction "2_2") (pintype "passive"))
      (node (ref "R42") (pin "2") (pinfunction "2_2") (pintype "passive"))
      (node (ref "R43") (pin "2") (pinfunction "2_2") (pintype "passive"))
      (node (ref "R44") (pin "2") (pinfunction "2_2") (pintype "passive"))
      (node (ref "R45") (pin "2") (pinfunction "2_2") (pintype "passive"))
      (node (ref "R46") (pin "2") (pinfunction "2_2") (pintype "passive"))
      (node (ref "R47") (pin "2") (pinfunction "2_2") (pintype "passive"))
      (node (ref "R48") (pin "2") (pinfunction "2_2") (pintype "passive"))
      (node (ref "R49") (pin "2") (pinfunction "2_2") (pintype "passive"))
      (node (ref "R50") (pin "2") (pinfunction "2_2") (pintype "passive"))
      (node (ref "R51") (pin "2") (pinfunction "2_2") (pintype "passive"))
      (node (ref "R52") (pin "2") (pinfunction "2_2") (pintype "passive"))
      (node (ref "R55") (pin "2") (pinfunction "2_2") (pintype "passive"))
      (node (ref "R56") (pin "2") (pinfunction "2_2") (pintype "passive"))
      (node (ref "R57") (pin "2") (pinfunction "2_2") (pintype "passive"))
      (node (ref "U1") (pin "12") (pinfunction "GND_12") (pintype "bidirectional"))
    )
    (net (code "30") (name "Net-(D1-PadC)") (class "Default")
      (node (ref "D1") (pin "C") (pinfunction "C_C") (pintype "passive"))
      (node (ref "R7") (pin "2") (pinfunction "2_2") (pintype "passive"))
    )
    (net (code "31") (name "Net-(D2-PadC)") (class "Default")
      (node (ref "D2") (pin "C") (pinfunction "C_C") (pintype "passive"))
      (node (ref "R8") (pin "2") (pinfunction "2_2") (pintype "passive"))
    )
    (net (code "32") (name "Net-(D3-PadC)") (class "Default")
      (node (ref "D3") (pin "C") (pinfunction "C_C") (pintype "passive"))
      (node (ref "R11") (pin "2") (pinfunction "2_2") (pintype "passive"))
    )
    (net (code "33") (name "Net-(D4-PadC)") (class "Default")
      (node (ref "D4") (pin "C") (pinfunction "C_C") (pintype "passive"))
      (node (ref "R12") (pin "2") (pinfunction "2_2") (pintype "passive"))
    )
    (net (code "34") (name "Net-(D5-PadC)") (class "Default")
      (node (ref "D5") (pin "C") (pinfunction "C_C") (pintype "passive"))
      (node (ref "R15") (pin "2") (pinfunction "2_2") (pintype "passive"))
    )
    (net (code "35") (name "Net-(D6-PadC)") (class "Default")
      (node (ref "D6") (pin "C") (pinfunction "C_C") (pintype "passive"))
      (node (ref "R16") (pin "2") (pinfunction "2_2") (pintype "passive"))
    )
    (net (code "36") (name "Net-(D7-PadC)") (class "Default")
      (node (ref "D7") (pin "C") (pinfunction "C_C") (pintype "passive"))
      (node (ref "R19") (pin "2") (pinfunction "2_2") (pintype "passive"))
    )
    (net (code "37") (name "Net-(D8-PadC)") (class "Default")
      (node (ref "D8") (pin "C") (pinfunction "C_C") (pintype "passive"))
      (node (ref "R20") (pin "2") (pinfunction "2_2") (pintype "passive"))
    )
    (net (code "38") (name "Net-(D9-PadC)") (class "Default")
      (node (ref "D9") (pin "C") (pinfunction "C_C") (pintype "passive"))
      (node (ref "R23") (pin "2") (pinfunction "2_2") (pintype "passive"))
    )
    (net (code "39") (name "Net-(D10-PadC)") (class "Default")
      (node (ref "D10") (pin "C") (pinfunction "C_C") (pintype "passive"))
      (node (ref "R24") (pin "2") (pinfunction "2_2") (pintype "passive"))
    )
    (net (code "40") (name "Net-(D11-PadC)") (class "Default")
      (node (ref "D11") (pin "C") (pinfunction "C_C") (pintype "passive"))
      (node (ref "R27") (pin "2") (pinfunction "2_2") (pintype "passive"))
    )
    (net (code "41") (name "Net-(D12-PadC)") (class "Default")
      (node (ref "D12") (pin "C") (pinfunction "C_C") (pintype "passive"))
      (node (ref "R28") (pin "2") (pinfunction "2_2") (pintype "passive"))
    )
    (net (code "42") (name "Net-(D13-PadC)") (class "Default")
      (node (ref "D13") (pin "C") (pinfunction "C_C") (pintype "passive"))
      (node (ref "R31") (pin "2") (pinfunction "2_2") (pintype "passive"))
    )
    (net (code "43") (name "Net-(D14-PadC)") (class "Default")
      (node (ref "D14") (pin "C") (pinfunction "C_C") (pintype "passive"))
      (node (ref "R32") (pin "2") (pinfunction "2_2") (pintype "passive"))
    )
    (net (code "44") (name "Net-(D15-PadC)") (class "Default")
      (node (ref "D15") (pin "C") (pinfunction "C_C") (pintype "passive"))
      (node (ref "R35") (pin "2") (pinfunction "2_2") (pintype "passive"))
    )
    (net (code "45") (name "Net-(D16-PadC)") (class "Default")
      (node (ref "D16") (pin "C") (pinfunction "C_C") (pintype "passive"))
      (node (ref "R36") (pin "2") (pinfunction "2_2") (pintype "passive"))
    )
    (net (code "46") (name "Net-(D17-PadC)") (class "Default")
      (node (ref "D17") (pin "C") (pinfunction "C_C") (pintype "passive"))
      (node (ref "R3") (pin "1") (pinfunction "1_1") (pintype "passive"))
    )
    (net (code "47") (name "Net-(D18-PadC)") (class "Default")
      (node (ref "D18") (pin "C") (pinfunction "C_C") (pintype "passive"))
      (node (ref "R4") (pin "1") (pinfunction "1_1") (pintype "passive"))
    )
    (net (code "48") (name "Net-(D19-C)") (class "Default")
      (node (ref "D19") (pin "K") (pinfunction "C_K") (pintype "passive"))
      (node (ref "IC2") (pin "1") (pinfunction "1B_1") (pintype "bidirectional"))
      (node (ref "R37") (pin "1") (pinfunction "1_1") (pintype "passive"))
      (node (ref "S1") (pin "2") (pinfunction "2_2") (pintype "bidirectional"))
    )
    (net (code "49") (name "Net-(D19-PadA)") (class "Default")
      (node (ref "D19") (pin "A") (pinfunction "A_A") (pintype "passive"))
      (node (ref "J3") (pin "1") (pinfunction "1_1") (pintype "passive"))
    )
    (net (code "50") (name "Net-(D20-C)") (class "Default")
      (node (ref "D20") (pin "K") (pinfunction "C_K") (pintype "passive"))
      (node (ref "IC2") (pin "2") (pinfunction "2B_2") (pintype "bidirectional"))
      (node (ref "R38") (pin "1") (pinfunction "1_1") (pintype "passive"))
      (node (ref "S2") (pin "2") (pinfunction "2_2") (pintype "bidirectional"))
    )
    (net (code "51") (name "Net-(D20-PadA)") (class "Default")
      (node (ref "D20") (pin "A") (pinfunction "A_A") (pintype "passive"))
      (node (ref "J3") (pin "2") (pinfunction "2_2") (pintype "passive"))
    )
    (net (code "52") (name "Net-(D21-C)") (class "Default")
      (node (ref "D21") (pin "K") (pinfunction "C_K") (pintype "passive"))
      (node (ref "IC2") (pin "3") (pinfunction "3B_3") (pintype "bidirectional"))
      (node (ref "R39") (pin "1") (pinfunction "1_1") (pintype "passive"))
      (node (ref "S3") (pin "2") (pinfunction "2_2") (pintype "bidirectional"))
    )
    (net (code "53") (name "Net-(D21-PadA)") (class "Default")
      (node (ref "D21") (pin "A") (pinfunction "A_A") (pintype "passive"))
      (node (ref "J3") (pin "3") (pinfunction "3_3") (pintype "passive"))
    )
    (net (code "54") (name "Net-(D22-C)") (class "Default")
      (node (ref "D22") (pin "K") (pinfunction "C_K") (pintype "passive"))
      (node (ref "IC2") (pin "4") (pinfunction "4B_4") (pintype "bidirectional"))
      (node (ref "R40") (pin "1") (pinfunction "1_1") (pintype "passive"))
      (node (ref "S4") (pin "2") (pinfunction "2_2") (pintype "bidirectional"))
    )
    (net (code "55") (name "Net-(D22-PadA)") (class "Default")
      (node (ref "D22") (pin "A") (pinfunction "A_A") (pintype "passive"))
      (node (ref "J3") (pin "4") (pinfunction "4_4") (pintype "passive"))
    )
    (net (code "56") (name "Net-(D23-C)") (class "Default")
      (node (ref "D23") (pin "K") (pinfunction "C_K") (pintype "passive"))
      (node (ref "IC2") (pin "5") (pinfunction "5B_5") (pintype "bidirectional"))
      (node (ref "R41") (pin "1") (pinfunction "1_1") (pintype "passive"))
      (node (ref "S5") (pin "2") (pinfunction "2_2") (pintype "bidirectional"))
    )
    (net (code "57") (name "Net-(D23-PadA)") (class "Default")
      (node (ref "D23") (pin "A") (pinfunction "A_A") (pintype "passive"))
      (node (ref "J3") (pin "5") (pinfunction "5_5") (pintype "passive"))
    )
    (net (code "58") (name "Net-(D24-C)") (class "Default")
      (node (ref "D24") (pin "K") (pinfunction "C_K") (pintype "passive"))
      (node (ref "IC2") (pin "6") (pinfunction "6B_6") (pintype "bidirectional"))
      (node (ref "R42") (pin "1") (pinfunction "1_1") (pintype "passive"))
      (node (ref "S6") (pin "2") (pinfunction "2_2") (pintype "bidirectional"))
    )
    (net (code "59") (name "Net-(D24-PadA)") (class "Default")
      (node (ref "D24") (pin "A") (pinfunction "A_A") (pintype "passive"))
      (node (ref "J3") (pin "6") (pinfunction "6_6") (pintype "passive"))
    )
    (net (code "60") (name "Net-(D25-C)") (class "Default")
      (node (ref "D25") (pin "K") (pinfunction "C_K") (pintype "passive"))
      (node (ref "IC2") (pin "7") (pinfunction "7B_7") (pintype "bidirectional"))
      (node (ref "R43") (pin "1") (pinfunction "1_1") (pintype "passive"))
      (node (ref "S7") (pin "2") (pinfunction "2_2") (pintype "bidirectional"))
    )
    (net (code "61") (name "Net-(D25-PadA)") (class "Default")
      (node (ref "D25") (pin "A") (pinfunction "A_A") (pintype "passive"))
      (node (ref "J3") (pin "7") (pinfunction "7_7") (pintype "passive"))
    )
    (net (code "62") (name "Net-(D26-C)") (class "Default")
      (node (ref "D26") (pin "K") (pinfunction "C_K") (pintype "passive"))
      (node (ref "IC2") (pin "8") (pinfunction "8B_8") (pintype "bidirectional"))
      (node (ref "R44") (pin "1") (pinfunction "1_1") (pintype "passive"))
      (node (ref "S8") (pin "2") (pinfunction "2_2") (pintype "bidirectional"))
    )
    (net (code "63") (name "Net-(D26-PadA)") (class "Default")
      (node (ref "D26") (pin "A") (pinfunction "A_A") (pintype "passive"))
      (node (ref "J3") (pin "8") (pinfunction "8_8") (pintype "passive"))
    )
    (net (code "64") (name "Net-(D27-C)") (class "Default")
      (node (ref "D27") (pin "K") (pinfunction "C_K") (pintype "passive"))
      (node (ref "IC1") (pin "1") (pinfunction "1B_1") (pintype "bidirectional"))
      (node (ref "R45") (pin "1") (pinfunction "1_1") (pintype "passive"))
      (node (ref "S9") (pin "2") (pinfunction "2_2") (pintype "bidirectional"))
    )
    (net (code "65") (name "Net-(D27-PadA)") (class "Default")
      (node (ref "D27") (pin "A") (pinfunction "A_A") (pintype "passive"))
      (node (ref "J13") (pin "1") (pinfunction "1_1") (pintype "passive"))
    )
    (net (code "66") (name "Net-(D28-C)") (class "Default")
      (node (ref "D28") (pin "K") (pinfunction "C_K") (pintype "passive"))
      (node (ref "IC1") (pin "2") (pinfunction "2B_2") (pintype "bidirectional"))
      (node (ref "R46") (pin "1") (pinfunction "1_1") (pintype "passive"))
      (node (ref "S10") (pin "2") (pinfunction "2_2") (pintype "bidirectional"))
    )
    (net (code "67") (name "Net-(D28-PadA)") (class "Default")
      (node (ref "D28") (pin "A") (pinfunction "A_A") (pintype "passive"))
      (node (ref "J13") (pin "2") (pinfunction "2_2") (pintype "passive"))
    )
    (net (code "68") (name "Net-(D29-C)") (class "Default")
      (node (ref "D29") (pin "K") (pinfunction "C_K") (pintype "passive"))
      (node (ref "IC1") (pin "3") (pinfunction "3B_3") (pintype "bidirectional"))
      (node (ref "R47") (pin "1") (pinfunction "1_1") (pintype "passive"))
      (node (ref "S11") (pin "2") (pinfunction "2_2") (pintype "bidirectional"))
    )
    (net (code "69") (name "Net-(D29-PadA)") (class "Default")
      (node (ref "D29") (pin "A") (pinfunction "A_A") (pintype "passive"))
      (node (ref "J13") (pin "3") (pinfunction "3_3") (pintype "passive"))
    )
    (net (code "70") (name "Net-(D30-C)") (class "Default")
      (node (ref "D30") (pin "K") (pinfunction "C_K") (pintype "passive"))
      (node (ref "IC1") (pin "4") (pinfunction "4B_4") (pintype "bidirectional"))
      (node (ref "R48") (pin "1") (pinfunction "1_1") (pintype "passive"))
      (node (ref "S12") (pin "2") (pinfunction "2_2") (pintype "bidirectional"))
    )
    (net (code "71") (name "Net-(D30-PadA)") (class "Default")
      (node (ref "D30") (pin "A") (pinfunction "A_A") (pintype "passive"))
      (node (ref "J13") (pin "4") (pinfunction "4_4") (pintype "passive"))
    )
    (net (code "72") (name "Net-(D31-C)") (class "Default")
      (node (ref "D31") (pin "K") (pinfunction "C_K") (pintype "passive"))
      (node (ref "IC1") (pin "5") (pinfunction "5B_5") (pintype "bidirectional"))
      (node (ref "R49") (pin "1") (pinfunction "1_1") (pintype "passive"))
      (node (ref "S13") (pin "2") (pinfunction "2_2") (pintype "bidirectional"))
    )
    (net (code "73") (name "Net-(D31-PadA)") (class "Default")
      (node (ref "D31") (pin "A") (pinfunction "A_A") (pintype "passive"))
      (node (ref "J13") (pin "5") (pinfunction "5_5") (pintype "passive"))
    )
    (net (code "74") (name "Net-(D32-C)") (class "Default")
      (node (ref "D32") (pin "K") (pinfunction "C_K") (pintype "passive"))
      (node (ref "IC1") (pin "6") (pinfunction "6B_6") (pintype "bidirectional"))
      (node (ref "R50") (pin "1") (pinfunction "1_1") (pintype "passive"))
      (node (ref "S14") (pin "2") (pinfunction "2_2") (pintype "bidirectional"))
    )
    (net (code "75") (name "Net-(D32-PadA)") (class "Default")
      (node (ref "D32") (pin "A") (pinfunction "A_A") (pintype "passive"))
      (node (ref "J13") (pin "6") (pinfunction "6_6") (pintype "passive"))
    )
    (net (code "76") (name "Net-(D33-C)") (class "Default")
      (node (ref "D33") (pin "K") (pinfunction "C_K") (pintype "passive"))
      (node (ref "IC1") (pin "7") (pinfunction "7B_7") (pintype "bidirectional"))
      (node (ref "R51") (pin "1") (pinfunction "1_1") (pintype "passive"))
      (node (ref "S15") (pin "2") (pinfunction "2_2") (pintype "bidirectional"))
    )
    (net (code "77") (name "Net-(D33-PadA)") (class "Default")
      (node (ref "D33") (pin "A") (pinfunction "A_A") (pintype "passive"))
      (node (ref "J13") (pin "7") (pinfunction "7_7") (pintype "passive"))
    )
    (net (code "78") (name "Net-(D34-C)") (class "Default")
      (node (ref "D34") (pin "K") (pinfunction "C_K") (pintype "passive"))
      (node (ref "IC1") (pin "8") (pinfunction "8B_8") (pintype "bidirectional"))
      (node (ref "R52") (pin "1") (pinfunction "1_1") (pintype "passive"))
      (node (ref "S16") (pin "2") (pinfunction "2_2") (pintype "bidirectional"))
    )
    (net (code "79") (name "Net-(D34-PadA)") (class "Default")
      (node (ref "D34") (pin "A") (pinfunction "A_A") (pintype "passive"))
      (node (ref "J13") (pin "8") (pinfunction "8_8") (pintype "passive"))
    )
    (net (code "80") (name "Net-(IC2-1C)") (class "Default")
      (node (ref "IC2") (pin "18") (pinfunction "1C_18") (pintype "bidirectional"))
      (node (ref "J5") (pin "1") (pinfunction "1_1") (pintype "passive"))
      (node (ref "R7") (pin "1") (pinfunction "1_1") (pintype "passive"))
    )
    (net (code "81") (name "Net-(IC2-2C)") (class "Default")
      (node (ref "IC2") (pin "17") (pinfunction "2C_17") (pintype "bidirectional"))
      (node (ref "J5") (pin "3") (pinfunction "3_3") (pintype "passive"))
      (node (ref "R8") (pin "1") (pinfunction "1_1") (pintype "passive"))
    )
    (net (code "82") (name "Net-(IC2-3C)") (class "Default")
      (node (ref "IC2") (pin "16") (pinfunction "3C_16") (pintype "bidirectional"))
      (node (ref "J7") (pin "1") (pinfunction "1_1") (pintype "passive"))
      (node (ref "R11") (pin "1") (pinfunction "1_1") (pintype "passive"))
    )
    (net (code "83") (name "Net-(IC2-4C)") (class "Default")
      (node (ref "IC2") (pin "15") (pinfunction "4C_15") (pintype "bidirectional"))
      (node (ref "J7") (pin "3") (pinfunction "3_3") (pintype "passive"))
      (node (ref "R12") (pin "1") (pinfunction "1_1") (pintype "passive"))
    )
    (net (code "84") (name "Net-(IC2-5C)") (class "Default")
      (node (ref "IC2") (pin "14") (pinfunction "5C_14") (pintype "bidirectional"))
      (node (ref "J9") (pin "1") (pinfunction "1_1") (pintype "passive"))
      (node (ref "R15") (pin "1") (pinfunction "1_1") (pintype "passive"))
    )
    (net (code "85") (name "Net-(IC2-6C)") (class "Default")
      (node (ref "IC2") (pin "13") (pinfunction "6C_13") (pintype "bidirectional"))
      (node (ref "J9") (pin "3") (pinfunction "3_3") (pintype "passive"))
      (node (ref "R16") (pin "1") (pinfunction "1_1") (pintype "passive"))
    )
    (net (code "86") (name "Net-(IC2-7C)") (class "Default")
      (node (ref "IC2") (pin "12") (pinfunction "7C_12") (pintype "bidirectional"))
      (node (ref "J11") (pin "1") (pinfunction "1_1") (pintype "passive"))
      (node (ref "R19") (pin "1") (pinfunction "1_1") (pintype "passive"))
    )
    (net (code "87") (name "Net-(IC2-8C)") (class "Default")
      (node (ref "IC2") (pin "11") (pinfunction "8C_11") (pintype "bidirectional"))
      (node (ref "J11") (pin "3") (pinfunction "3_3") (pintype "passive"))
      (node (ref "R20") (pin "1") (pinfunction "1_1") (pintype "passive"))
    )
    (net (code "88") (name "Net-(U1-A0)") (class "Default")
      (node (ref "R57") (pin "1") (pinfunction "1_1") (pintype "passive"))
      (node (ref "U1") (pin "1") (pinfunction "A0_1") (pintype "bidirectional"))
    )
    (net (code "89") (name "Net-(U1-A1)") (class "Default")
      (node (ref "R56") (pin "1") (pinfunction "1_1") (pintype "passive"))
      (node (ref "U1") (pin "2") (pinfunction "A1_2") (pintype "bidirectional"))
    )
    (net (code "90") (name "Net-(U1-A2)") (class "Default")
      (node (ref "R55") (pin "1") (pinfunction "1_1") (pintype "passive"))
      (node (ref "U1") (pin "21") (pinfunction "A2_21") (pintype "bidirectional"))
    )
    (net (code "91") (name "VCC") (class "Default")
      (node (ref "D1") (pin "A") (pinfunction "A_A") (pintype "passive"))
      (node (ref "D10") (pin "A") (pinfunction "A_A") (pintype "passive"))
      (node (ref "D11") (pin "A") (pinfunction "A_A") (pintype "passive"))
      (node (ref "D12") (pin "A") (pinfunction "A_A") (pintype "passive"))
      (node (ref "D13") (pin "A") (pinfunction "A_A") (pintype "passive"))
      (node (ref "D14") (pin "A") (pinfunction "A_A") (pintype "passive"))
      (node (ref "D15") (pin "A") (pinfunction "A_A") (pintype "passive"))
      (node (ref "D16") (pin "A") (pinfunction "A_A") (pintype "passive"))
      (node (ref "D18") (pin "A") (pinfunction "A_A") (pintype "passive"))
      (node (ref "D2") (pin "A") (pinfunction "A_A") (pintype "passive"))
      (node (ref "D3") (pin "A") (pinfunction "A_A") (pintype "passive"))
      (node (ref "D4") (pin "A") (pinfunction "A_A") (pintype "passive"))
      (node (ref "D5") (pin "A") (pinfunction "A_A") (pintype "passive"))
      (node (ref "D6") (pin "A") (pinfunction "A_A") (pintype "passive"))
      (node (ref "D7") (pin "A") (pinfunction "A_A") (pintype "passive"))
      (node (ref "D8") (pin "A") (pinfunction "A_A") (pintype "passive"))
      (node (ref "D9") (pin "A") (pinfunction "A_A") (pintype "passive"))
      (node (ref "IC1") (pin "10") (pinfunction "COM_10") (pintype "bidirectional"))
      (node (ref "IC2") (pin "10") (pinfunction "COM_10") (pintype "bidirectional"))
      (node (ref "J1") (pin "1") (pinfunction "1_1") (pintype "passive"))
      (node (ref "J11") (pin "2") (pinfunction "2_2") (pintype "passive"))
      (node (ref "J11") (pin "4") (pinfunction "4_4") (pintype "passive"))
      (node (ref "J15") (pin "2") (pinfunction "2_2") (pintype "passive"))
      (node (ref "J15") (pin "4") (pinfunction "4_4") (pintype "passive"))
      (node (ref "J17") (pin "2") (pinfunction "2_2") (pintype "passive"))
      (node (ref "J17") (pin "4") (pinfunction "4_4") (pintype "passive"))
      (node (ref "J19") (pin "2") (pinfunction "2_2") (pintype "passive"))
      (node (ref "J19") (pin "4") (pinfunction "4_4") (pintype "passive"))
      (node (ref "J20") (pin "2") (pinfunction "2_2") (pintype "passive"))
      (node (ref "J20") (pin "4") (pinfunction "4_4") (pintype "passive"))
      (node (ref "J5") (pin "2") (pinfunction "2_2") (pintype "passive"))
      (node (ref "J5") (pin "4") (pinfunction "4_4") (pintype "passive"))
      (node (ref "J7") (pin "2") (pinfunction "2_2") (pintype "passive"))
      (node (ref "J7") (pin "4") (pinfunction "4_4") (pintype "passive"))
      (node (ref "J9") (pin "2") (pinfunction "2_2") (pintype "passive"))
      (node (ref "J9") (pin "4") (pinfunction "4_4") (pintype "passive"))
    )
    (net (code "92") (name "unconnected-(S1-Pad1)") (class "Default")
      (node (ref "S1") (pin "1") (pinfunction "1_1") (pintype "bidirectional"))
    )
    (net (code "93") (name "unconnected-(S1-Pad4)") (class "Default")
      (node (ref "S1") (pin "4") (pinfunction "4_4") (pintype "bidirectional"))
    )
    (net (code "94") (name "unconnected-(S2-Pad1)") (class "Default")
      (node (ref "S2") (pin "1") (pinfunction "1_1") (pintype "bidirectional"))
    )
    (net (code "95") (name "unconnected-(S2-Pad4)") (class "Default")
      (node (ref "S2") (pin "4") (pinfunction "4_4") (pintype "bidirectional"))
    )
    (net (code "96") (name "unconnected-(S3-Pad1)") (class "Default")
      (node (ref "S3") (pin "1") (pinfunction "1_1") (pintype "bidirectional"))
    )
    (net (code "97") (name "unconnected-(S3-Pad4)") (class "Default")
      (node (ref "S3") (pin "4") (pinfunction "4_4") (pintype "bidirectional"))
    )
    (net (code "98") (name "unconnected-(S4-Pad1)") (class "Default")
      (node (ref "S4") (pin "1") (pinfunction "1_1") (pintype "bidirectional"))
    )
    (net (code "99") (name "unconnected-(S4-Pad4)") (class "Default")
      (node (ref "S4") (pin "4") (pinfunction "4_4") (pintype "bidirectional"))
    )
    (net (code "100") (name "unconnected-(S5-Pad1)") (class "Default")
      (node (ref "S5") (pin "1") (pinfunction "1_1") (pintype "bidirectional"))
    )
    (net (code "101") (name "unconnected-(S5-Pad4)") (class "Default")
      (node (ref "S5") (pin "4") (pinfunction "4_4") (pintype "bidirectional"))
    )
    (net (code "102") (name "unconnected-(S6-Pad1)") (class "Default")
      (node (ref "S6") (pin "1") (pinfunction "1_1") (pintype "bidirectional"))
    )
    (net (code "103") (name "unconnected-(S6-Pad4)") (class "Default")
      (node (ref "S6") (pin "4") (pinfunction "4_4") (pintype "bidirectional"))
    )
    (net (code "104") (name "unconnected-(S7-Pad1)") (class "Default")
      (node (ref "S7") (pin "1") (pinfunction "1_1") (pintype "bidirectional"))
    )
    (net (code "105") (name "unconnected-(S7-Pad4)") (class "Default")
      (node (ref "S7") (pin "4") (pinfunction "4_4") (pintype "bidirectional"))
    )
    (net (code "106") (name "unconnected-(S8-Pad1)") (class "Default")
      (node (ref "S8") (pin "1") (pinfunction "1_1") (pintype "bidirectional"))
    )
    (net (code "107") (name "unconnected-(S8-Pad4)") (class "Default")
      (node (ref "S8") (pin "4") (pinfunction "4_4") (pintype "bidirectional"))
    )
    (net (code "108") (name "unconnected-(S9-Pad1)") (class "Default")
      (node (ref "S9") (pin "1") (pinfunction "1_1") (pintype "bidirectional"))
    )
    (net (code "109") (name "unconnected-(S9-Pad4)") (class "Default")
      (node (ref "S9") (pin "4") (pinfunction "4_4") (pintype "bidirectional"))
    )
    (net (code "110") (name "unconnected-(S10-Pad1)") (class "Default")
      (node (ref "S10") (pin "1") (pinfunction "1_1") (pintype "bidirectional"))
    )
    (net (code "111") (name "unconnected-(S10-Pad4)") (class "Default")
      (node (ref "S10") (pin "4") (pinfunction "4_4") (pintype "bidirectional"))
    )
    (net (code "112") (name "unconnected-(S11-Pad1)") (class "Default")
      (node (ref "S11") (pin "1") (pinfunction "1_1") (pintype "bidirectional"))
    )
    (net (code "113") (name "unconnected-(S11-Pad4)") (class "Default")
      (node (ref "S11") (pin "4") (pinfunction "4_4") (pintype "bidirectional"))
    )
    (net (code "114") (name "unconnected-(S12-Pad1)") (class "Default")
      (node (ref "S12") (pin "1") (pinfunction "1_1") (pintype "bidirectional"))
    )
    (net (code "115") (name "unconnected-(S12-Pad4)") (class "Default")
      (node (ref "S12") (pin "4") (pinfunction "4_4") (pintype "bidirectional"))
    )
    (net (code "116") (name "unconnected-(S13-Pad1)") (class "Default")
      (node (ref "S13") (pin "1") (pinfunction "1_1") (pintype "bidirectional"))
    )
    (net (code "117") (name "unconnected-(S13-Pad4)") (class "Default")
      (node (ref "S13") (pin "4") (pinfunction "4_4") (pintype "bidirectional"))
    )
    (net (code "118") (name "unconnected-(S14-Pad1)") (class "Default")
      (node (ref "S14") (pin "1") (pinfunction "1_1") (pintype "bidirectional"))
    )
    (net (code "119") (name "unconnected-(S14-Pad4)") (class "Default")
      (node (ref "S14") (pin "4") (pinfunction "4_4") (pintype "bidirectional"))
    )
    (net (code "120") (name "unconnected-(S15-Pad1)") (class "Default")
      (node (ref "S15") (pin "1") (pinfunction "1_1") (pintype "bidirectional"))
    )
    (net (code "121") (name "unconnected-(S15-Pad4)") (class "Default")
      (node (ref "S15") (pin "4") (pinfunction "4_4") (pintype "bidirectional"))
    )
    (net (code "122") (name "unconnected-(S16-Pad1)") (class "Default")
      (node (ref "S16") (pin "1") (pinfunction "1_1") (pintype "bidirectional"))
    )
    (net (code "123") (name "unconnected-(S16-Pad4)") (class "Default")
      (node (ref "S16") (pin "4") (pinfunction "4_4") (pintype "bidirectional"))
    )
  )
)
